# RX.net
KiCad netlist of a schematic drawn in EAGLE
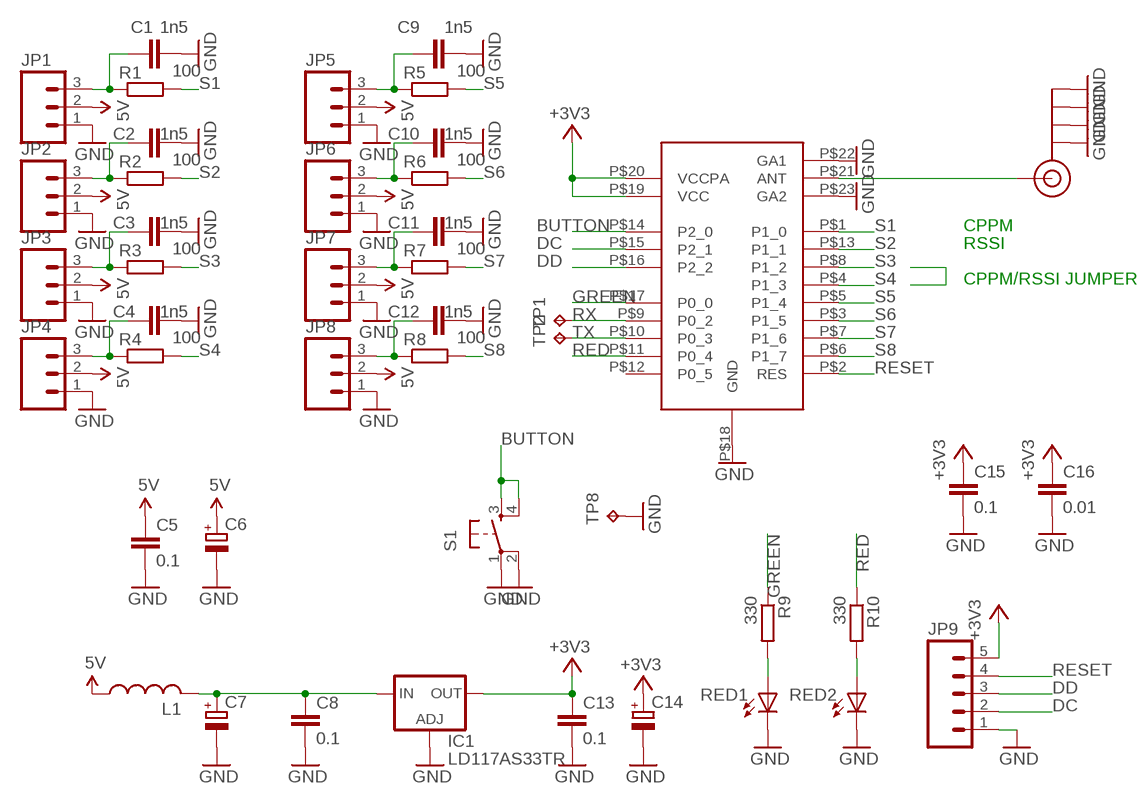
[diagram p0: schematic, sheet 1]

(export (version "E")
  (design (tool "Eeschema 10.0.6"))
  (components
    (comp (ref "C1")
      (value "1n5")
      (footprint "eagle-import:C0603")
      (libsource (lib "eagle-import") (part "C-EUC0603"))
    )
    (comp (ref "C2")
      (value "1n5")
      (footprint "eagle-import:C0603")
      (libsource (lib "eagle-import") (part "C-EUC0603"))
    )
    (comp (ref "C3")
      (value "1n5")
      (footprint "eagle-import:C0603")
      (libsource (lib "eagle-import") (part "C-EUC0603"))
    )
    (comp (ref "C4")
      (value "1n5")
      (footprint "eagle-import:C0603")
      (libsource (lib "eagle-import") (part "C-EUC0603"))
    )
    (comp (ref "C5")
      (value "0.1")
      (footprint "eagle-import:C0603")
      (libsource (lib "eagle-import") (part "C-EUC0603"))
    )
    (comp (ref "C6")
      (value "CPOL-EUCT3216")
      (footprint "eagle-import:CT3216")
      (libsource (lib "eagle-import") (part "CPOL-EUCT3216"))
    )
    (comp (ref "C7")
      (value "CPOL-EUCT3216")
      (footprint "eagle-import:CT3216")
      (libsource (lib "eagle-import") (part "CPOL-EUCT3216"))
    )
    (comp (ref "C8")
      (value "0.1")
      (footprint "eagle-import:C0603")
      (libsource (lib "eagle-import") (part "C-EUC0603"))
    )
    (comp (ref "C9")
      (value "1n5")
      (footprint "eagle-import:C0603")
      (libsource (lib "eagle-import") (part "C-EUC0603"))
    )
    (comp (ref "C10")
      (value "1n5")
      (footprint "eagle-import:C0603")
      (libsource (lib "eagle-import") (part "C-EUC0603"))
    )
    (comp (ref "C11")
      (value "1n5")
      (footprint "eagle-import:C0603")
      (libsource (lib "eagle-import") (part "C-EUC0603"))
    )
    (comp (ref "C12")
      (value "1n5")
      (footprint "eagle-import:C0603")
      (libsource (lib "eagle-import") (part "C-EUC0603"))
    )
    (comp (ref "C13")
      (value "0.1")
      (footprint "eagle-import:C0603")
      (libsource (lib "eagle-import") (part "C-EUC0603"))
    )
    (comp (ref "C14")
      (value "CPOL-EUCT3216")
      (footprint "eagle-import:CT3216")
      (libsource (lib "eagle-import") (part "CPOL-EUCT3216"))
    )
    (comp (ref "C15")
      (value "0.1")
      (footprint "eagle-import:C0603")
      (libsource (lib "eagle-import") (part "C-EUC0603"))
    )
    (comp (ref "C16")
      (value "0.01")
      (footprint "eagle-import:C0603")
      (libsource (lib "eagle-import") (part "C-EUC0603"))
    )
    (comp (ref "IC1")
      (value "LD117AS33TR")
      (footprint "eagle-import:SOT223")
      (libsource (lib "eagle-import") (part "LD117A?S33TR"))
    )
    (comp (ref "J$1")
      (value "SMA_EDGE")
      (footprint "eagle-import:SMA-EDGE")
      (libsource (lib "eagle-import") (part "SMA_EDGE"))
    )
    (comp (ref "JP1")
      (value "M03PTH")
      (footprint "eagle-import:1X03")
      (libsource (lib "eagle-import") (part "M03PTH"))
    )
    (comp (ref "JP2")
      (value "M03PTH")
      (footprint "eagle-import:1X03")
      (libsource (lib "eagle-import") (part "M03PTH"))
    )
    (comp (ref "JP3")
      (value "M03PTH")
      (footprint "eagle-import:1X03")
      (libsource (lib "eagle-import") (part "M03PTH"))
    )
    (comp (ref "JP4")
      (value "M03PTH")
      (footprint "eagle-import:1X03")
      (libsource (lib "eagle-import") (part "M03PTH"))
    )
    (comp (ref "JP5")
      (value "M03PTH")
      (footprint "eagle-import:1X03")
      (libsource (lib "eagle-import") (part "M03PTH"))
    )
    (comp (ref "JP6")
      (value "M03PTH")
      (footprint "eagle-import:1X03")
      (libsource (lib "eagle-import") (part "M03PTH"))
    )
    (comp (ref "JP7")
      (value "M03PTH")
      (footprint "eagle-import:1X03")
      (libsource (lib "eagle-import") (part "M03PTH"))
    )
    (comp (ref "JP8")
      (value "M03PTH")
      (footprint "eagle-import:1X03")
      (libsource (lib "eagle-import") (part "M03PTH"))
    )
    (comp (ref "JP9")
      (value "M05PTH")
      (footprint "eagle-import:1X05")
      (libsource (lib "eagle-import") (part "M05PTH"))
    )
    (comp (ref "L1")
      (value "L-USL2012C")
      (footprint "eagle-import:L2012C")
      (libsource (lib "eagle-import") (part "L-USL2012C"))
    )
    (comp (ref "R1")
      (value "100")
      (footprint "eagle-import:MINI_MELF-0102R")
      (libsource (lib "eagle-import") (part "R-EU_MELF0102R"))
    )
    (comp (ref "R2")
      (value "100")
      (footprint "eagle-import:MINI_MELF-0102R")
      (libsource (lib "eagle-import") (part "R-EU_MELF0102R"))
    )
    (comp (ref "R3")
      (value "100")
      (footprint "eagle-import:MINI_MELF-0102R")
      (libsource (lib "eagle-import") (part "R-EU_MELF0102R"))
    )
    (comp (ref "R4")
      (value "100")
      (footprint "eagle-import:MINI_MELF-0102R")
      (libsource (lib "eagle-import") (part "R-EU_MELF0102R"))
    )
    (comp (ref "R5")
      (value "100")
      (footprint "eagle-import:MINI_MELF-0102R")
      (libsource (lib "eagle-import") (part "R-EU_MELF0102R"))
    )
    (comp (ref "R6")
      (value "100")
      (footprint "eagle-import:MINI_MELF-0102R")
      (libsource (lib "eagle-import") (part "R-EU_MELF0102R"))
    )
    (comp (ref "R7")
      (value "100")
      (footprint "eagle-import:MINI_MELF-0102R")
      (libsource (lib "eagle-import") (part "R-EU_MELF0102R"))
    )
    (comp (ref "R8")
      (value "100")
      (footprint "eagle-import:MINI_MELF-0102R")
      (libsource (lib "eagle-import") (part "R-EU_MELF0102R"))
    )
    (comp (ref "R9")
      (value "330")
      (footprint "eagle-import:MINI_MELF-0102R")
      (libsource (lib "eagle-import") (part "R-EU_MELF0102R"))
    )
    (comp (ref "R10")
      (value "330")
      (footprint "eagle-import:MINI_MELF-0102R")
      (libsource (lib "eagle-import") (part "R-EU_MELF0102R"))
    )
    (comp (ref "RED1")
      (value "LEDCHIPLED_1206")
      (footprint "eagle-import:CHIPLED_1206")
      (libsource (lib "eagle-import") (part "LEDCHIPLED_1206"))
    )
    (comp (ref "RED2")
      (value "LEDCHIPLED_1206")
      (footprint "eagle-import:CHIPLED_1206")
      (libsource (lib "eagle-import") (part "LEDCHIPLED_1206"))
    )
    (comp (ref "S1")
      (value "TAC_SWITCHSMD")
      (footprint "eagle-import:TACTILE_SWITCH_SMD")
      (libsource (lib "eagle-import") (part "TAC_SWITCHSMD"))
    )
    (comp (ref "TP1")
      (value "TPB1,27")
      (footprint "eagle-import:B1,27")
      (libsource (lib "eagle-import") (part "TPB1,27"))
    )
    (comp (ref "TP2")
      (value "TPB1,27")
      (footprint "eagle-import:B1,27")
      (libsource (lib "eagle-import") (part "TPB1,27"))
    )
    (comp (ref "TP8")
      (value "TPB1,27")
      (footprint "eagle-import:B1,27")
      (libsource (lib "eagle-import") (part "TPB1,27"))
    )
    (comp (ref "U$1")
      (value "CC1110_PA")
      (footprint "eagle-import:CC1110_PA")
      (libsource (lib "eagle-import") (part "CC1110_PA"))
    )
  )
  (nets
    (net (code "1") (name "+3V3") (class "Default")
      (node (ref "C13") (pin "1") (pinfunction "1_1") (pintype "passive"))
      (node (ref "C14") (pin "+") (pinfunction "+_+") (pintype "passive"))
      (node (ref "C15") (pin "1") (pinfunction "1_1") (pintype "passive"))
      (node (ref "C16") (pin "1") (pinfunction "1_1") (pintype "passive"))
      (node (ref "IC1") (pin "4") (pinfunction "OUT_4") (pintype "passive"))
      (node (ref "JP9") (pin "5") (pinfunction "5_5") (pintype "passive"))
      (node (ref "U$1") (pin "P$19") (pinfunction "VCC_P$19") (pintype "bidirectional"))
      (node (ref "U$1") (pin "P$20") (pinfunction "VCCPA_P$20") (pintype "bidirectional"))
    )
    (net (code "2") (name "/BUTTON") (class "Default")
      (node (ref "S1") (pin "3") (pinfunction "3_3") (pintype "passive"))
      (node (ref "S1") (pin "4") (pinfunction "4_4") (pintype "passive"))
      (node (ref "U$1") (pin "P$14") (pinfunction "P2_0_P$14") (pintype "bidirectional"))
    )
    (net (code "3") (name "/DC") (class "Default")
      (node (ref "JP9") (pin "2") (pinfunction "2_2") (pintype "passive"))
      (node (ref "U$1") (pin "P$15") (pinfunction "P2_1_P$15") (pintype "bidirectional"))
    )
    (net (code "4") (name "/DD") (class "Default")
      (node (ref "JP9") (pin "3") (pinfunction "3_3") (pintype "passive"))
      (node (ref "U$1") (pin "P$16") (pinfunction "P2_2_P$16") (pintype "bidirectional"))
    )
    (net (code "5") (name "/GREEN") (class "Default")
      (node (ref "R9") (pin "1") (pinfunction "1_1") (pintype "passive"))
      (node (ref "U$1") (pin "P$17") (pinfunction "P0_0_P$17") (pintype "bidirectional"))
    )
    (net (code "6") (name "/RED") (class "Default")
      (node (ref "R10") (pin "1") (pinfunction "1_1") (pintype "passive"))
      (node (ref "U$1") (pin "P$11") (pinfunction "P0_4_P$11") (pintype "bidirectional"))
    )
    (net (code "7") (name "/RESET") (class "Default")
      (node (ref "JP9") (pin "4") (pinfunction "4_4") (pintype "passive"))
      (node (ref "U$1") (pin "P$2") (pinfunction "RES_P$2") (pintype "bidirectional"))
    )
    (net (code "8") (name "/RX") (class "Default")
      (node (ref "TP1") (pin "TP") (pinfunction "TP_TP") (pintype "input"))
      (node (ref "U$1") (pin "P$9") (pinfunction "P0_2_P$9") (pintype "bidirectional"))
    )
    (net (code "9") (name "/S1") (class "Default")
      (node (ref "R1") (pin "2") (pinfunction "2_2") (pintype "passive"))
      (node (ref "U$1") (pin "P$1") (pinfunction "P1_0_P$1") (pintype "bidirectional"))
    )
    (net (code "10") (name "/S2") (class "Default")
      (node (ref "R2") (pin "2") (pinfunction "2_2") (pintype "passive"))
      (node (ref "U$1") (pin "P$13") (pinfunction "P1_1_P$13") (pintype "bidirectional"))
    )
    (net (code "11") (name "/S3") (class "Default")
      (node (ref "R3") (pin "2") (pinfunction "2_2") (pintype "passive"))
      (node (ref "U$1") (pin "P$8") (pinfunction "P1_2_P$8") (pintype "bidirectional"))
    )
    (net (code "12") (name "/S4") (class "Default")
      (node (ref "R4") (pin "2") (pinfunction "2_2") (pintype "passive"))
      (node (ref "U$1") (pin "P$4") (pinfunction "P1_3_P$4") (pintype "bidirectional"))
    )
    (net (code "13") (name "/S5") (class "Default")
      (node (ref "R5") (pin "2") (pinfunction "2_2") (pintype "passive"))
      (node (ref "U$1") (pin "P$5") (pinfunction "P1_4_P$5") (pintype "bidirectional"))
    )
    (net (code "14") (name "/S6") (class "Default")
      (node (ref "R6") (pin "2") (pinfunction "2_2") (pintype "passive"))
      (node (ref "U$1") (pin "P$3") (pinfunction "P1_5_P$3") (pintype "bidirectional"))
    )
    (net (code "15") (name "/S7") (class "Default")
      (node (ref "R7") (pin "2") (pinfunction "2_2") (pintype "passive"))
      (node (ref "U$1") (pin "P$7") (pinfunction "P1_6_P$7") (pintype "bidirectional"))
    )
    (net (code "16") (name "/S8") (class "Default")
      (node (ref "R8") (pin "2") (pinfunction "2_2") (pintype "passive"))
      (node (ref "U$1") (pin "P$6") (pinfunction "P1_7_P$6") (pintype "bidirectional"))
    )
    (net (code "17") (name "/TX") (class "Default")
      (node (ref "TP2") (pin "TP") (pinfunction "TP_TP") (pintype "input"))
      (node (ref "U$1") (pin "P$10") (pinfunction "P0_3_P$10") (pintype "bidirectional"))
    )
    (net (code "18") (name "5V") (class "Default")
      (node (ref "C5") (pin "1") (pinfunction "1_1") (pintype "passive"))
      (node (ref "C6") (pin "+") (pinfunction "+_+") (pintype "passive"))
      (node (ref "JP1") (pin "2") (pinfunction "2_2") (pintype "passive"))
      (node (ref "JP2") (pin "2") (pinfunction "2_2") (pintype "passive"))
      (node (ref "JP3") (pin "2") (pinfunction "2_2") (pintype "passive"))
      (node (ref "JP4") (pin "2") (pinfunction "2_2") (pintype "passive"))
      (node (ref "JP5") (pin "2") (pinfunction "2_2") (pintype "passive"))
      (node (ref "JP6") (pin "2") (pinfunction "2_2") (pintype "passive"))
      (node (ref "JP7") (pin "2") (pinfunction "2_2") (pintype "passive"))
      (node (ref "JP8") (pin "2") (pinfunction "2_2") (pintype "passive"))
      (node (ref "L1") (pin "1") (pinfunction "1_1") (pintype "passive"))
    )
    (net (code "19") (name "GND") (class "Default")
      (node (ref "C1") (pin "2") (pinfunction "2_2") (pintype "passive"))
      (node (ref "C10") (pin "2") (pinfunction "2_2") (pintype "passive"))
      (node (ref "C11") (pin "2") (pinfunction "2_2") (pintype "passive"))
      (node (ref "C12") (pin "2") (pinfunction "2_2") (pintype "passive"))
      (node (ref "C13") (pin "2") (pinfunction "2_2") (pintype "passive"))
      (node (ref "C14") (pin "-") (pinfunction "-_-") (pintype "passive"))
      (node (ref "C15") (pin "2") (pinfunction "2_2") (pintype "passive"))
      (node (ref "C16") (pin "2") (pinfunction "2_2") (pintype "passive"))
      (node (ref "C2") (pin "2") (pinfunction "2_2") (pintype "passive"))
      (node (ref "C3") (pin "2") (pinfunction "2_2") (pintype "passive"))
      (node (ref "C4") (pin "2") (pinfunction "2_2") (pintype "passive"))
      (node (ref "C5") (pin "2") (pinfunction "2_2") (pintype "passive"))
      (node (ref "C6") (pin "-") (pinfunction "-_-") (pintype "passive"))
      (node (ref "C7") (pin "-") (pinfunction "-_-") (pintype "passive"))
      (node (ref "C8") (pin "2") (pinfunction "2_2") (pintype "passive"))
      (node (ref "C9") (pin "2") (pinfunction "2_2") (pintype "passive"))
      (node (ref "IC1") (pin "1") (pinfunction "ADJ_1") (pintype "input"))
      (node (ref "J$1") (pin "GND@0") (pinfunction "GND_GND@0") (pintype "bidirectional"))
      (node (ref "J$1") (pin "GND@1") (pinfunction "GND_GND@1") (pintype "bidirectional"))
      (node (ref "J$1") (pin "GND@2") (pinfunction "GND_GND@2") (pintype "bidirectional"))
      (node (ref "J$1") (pin "GND@3") (pinfunction "GND_GND@3") (pintype "bidirectional"))
      (node (ref "JP1") (pin "1") (pinfunction "1_1") (pintype "passive"))
      (node (ref "JP2") (pin "1") (pinfunction "1_1") (pintype "passive"))
      (node (ref "JP3") (pin "1") (pinfunction "1_1") (pintype "passive"))
      (node (ref "JP4") (pin "1") (pinfunction "1_1") (pintype "passive"))
      (node (ref "JP5") (pin "1") (pinfunction "1_1") (pintype "passive"))
      (node (ref "JP6") (pin "1") (pinfunction "1_1") (pintype "passive"))
      (node (ref "JP7") (pin "1") (pinfunction "1_1") (pintype "passive"))
      (node (ref "JP8") (pin "1") (pinfunction "1_1") (pintype "passive"))
      (node (ref "JP9") (pin "1") (pinfunction "1_1") (pintype "passive"))
      (node (ref "RED1") (pin "C") (pinfunction "C_C") (pintype "passive"))
      (node (ref "RED2") (pin "C") (pinfunction "C_C") (pintype "passive"))
      (node (ref "S1") (pin "1") (pinfunction "1_1") (pintype "passive"))
      (node (ref "S1") (pin "2") (pinfunction "2_2") (pintype "passive"))
      (node (ref "TP8") (pin "TP") (pinfunction "TP_TP") (pintype "input"))
      (node (ref "U$1") (pin "P$18") (pinfunction "GND_P$18") (pintype "bidirectional"))
      (node (ref "U$1") (pin "P$22") (pinfunction "GA1_P$22") (pintype "bidirectional"))
      (node (ref "U$1") (pin "P$23") (pinfunction "GA2_P$23") (pintype "bidirectional"))
    )
    (net (code "20") (name "Net-(C1-Pad1)") (class "Default")
      (node (ref "C1") (pin "1") (pinfunction "1_1") (pintype "passive"))
      (node (ref "JP1") (pin "3") (pinfunction "3_3") (pintype "passive"))
      (node (ref "R1") (pin "1") (pinfunction "1_1") (pintype "passive"))
    )
    (net (code "21") (name "Net-(C2-Pad1)") (class "Default")
      (node (ref "C2") (pin "1") (pinfunction "1_1") (pintype "passive"))
      (node (ref "JP2") (pin "3") (pinfunction "3_3") (pintype "passive"))
      (node (ref "R2") (pin "1") (pinfunction "1_1") (pintype "passive"))
    )
    (net (code "22") (name "Net-(C3-Pad1)") (class "Default")
      (node (ref "C3") (pin "1") (pinfunction "1_1") (pintype "passive"))
      (node (ref "JP3") (pin "3") (pinfunction "3_3") (pintype "passive"))
      (node (ref "R3") (pin "1") (pinfunction "1_1") (pintype "passive"))
    )
    (net (code "23") (name "Net-(C4-Pad1)") (class "Default")
      (node (ref "C4") (pin "1") (pinfunction "1_1") (pintype "passive"))
      (node (ref "JP4") (pin "3") (pinfunction "3_3") (pintype "passive"))
      (node (ref "R4") (pin "1") (pinfunction "1_1") (pintype "passive"))
    )
    (net (code "24") (name "Net-(C9-Pad1)") (class "Default")
      (node (ref "C9") (pin "1") (pinfunction "1_1") (pintype "passive"))
      (node (ref "JP5") (pin "3") (pinfunction "3_3") (pintype "passive"))
      (node (ref "R5") (pin "1") (pinfunction "1_1") (pintype "passive"))
    )
    (net (code "25") (name "Net-(C10-Pad1)") (class "Default")
      (node (ref "C10") (pin "1") (pinfunction "1_1") (pintype "passive"))
      (node (ref "JP6") (pin "3") (pinfunction "3_3") (pintype "passive"))
      (node (ref "R6") (pin "1") (pinfunction "1_1") (pintype "passive"))
    )
    (net (code "26") (name "Net-(C11-Pad1)") (class "Default")
      (node (ref "C11") (pin "1") (pinfunction "1_1") (pintype "passive"))
      (node (ref "JP7") (pin "3") (pinfunction "3_3") (pintype "passive"))
      (node (ref "R7") (pin "1") (pinfunction "1_1") (pintype "passive"))
    )
    (net (code "27") (name "Net-(C12-Pad1)") (class "Default")
      (node (ref "C12") (pin "1") (pinfunction "1_1") (pintype "passive"))
      (node (ref "JP8") (pin "3") (pinfunction "3_3") (pintype "passive"))
      (node (ref "R8") (pin "1") (pinfunction "1_1") (pintype "passive"))
    )
    (net (code "28") (name "Net-(IC1-IN)") (class "Default")
      (node (ref "C7") (pin "+") (pinfunction "+_+") (pintype "passive"))
      (node (ref "C8") (pin "1") (pinfunction "1_1") (pintype "passive"))
      (node (ref "IC1") (pin "3") (pinfunction "IN_3") (pintype "input"))
      (node (ref "L1") (pin "2") (pinfunction "2_2") (pintype "passive"))
    )
    (net (code "29") (name "Net-(J$1-SIGNAL)") (class "Default")
      (node (ref "J$1") (pin "SIG") (pinfunction "SIGNAL_SIG") (pintype "bidirectional"))
      (node (ref "U$1") (pin "P$21") (pinfunction "ANT_P$21") (pintype "bidirectional"))
    )
    (net (code "30") (name "Net-(R9-Pad2)") (class "Default")
      (node (ref "R9") (pin "2") (pinfunction "2_2") (pintype "passive"))
      (node (ref "RED1") (pin "A") (pinfunction "A_A") (pintype "passive"))
    )
    (net (code "31") (name "Net-(R10-Pad2)") (class "Default")
      (node (ref "R10") (pin "2") (pinfunction "2_2") (pintype "passive"))
      (node (ref "RED2") (pin "A") (pinfunction "A_A") (pintype "passive"))
    )
    (net (code "32") (name "unconnected-(U$1-P0_5-PadP$12)") (class "Default")
      (node (ref "U$1") (pin "P$12") (pinfunction "P0_5_P$12") (pintype "bidirectional"))
    )
  )
)
